# Alice.net
KiCad netlist of a schematic drawn in EAGLE
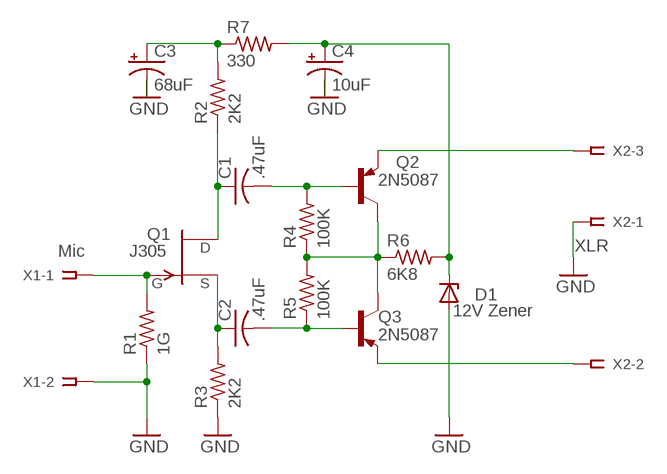
[diagram p0: schematic, sheet 1]

(export (version "E")
  (design (tool "Eeschema 10.0.6"))
  (components
    (comp (ref "C1")
      (value ".47uF")
      (footprint "eagle-import:C075-052X106")
      (libsource (lib "eagle-import") (part "C-US075-052X106"))
    )
    (comp (ref "C2")
      (value ".47uF")
      (footprint "eagle-import:C075-052X106")
      (libsource (lib "eagle-import") (part "C-US075-052X106"))
    )
    (comp (ref "C3")
      (value "68uF")
      (footprint "eagle-import:E3,5-10")
      (libsource (lib "eagle-import") (part "CPOL-USE3.5-10"))
    )
    (comp (ref "C4")
      (value "10uF")
      (footprint "eagle-import:E1,8-4")
      (libsource (lib "eagle-import") (part "CPOL-USE1.8-4"))
    )
    (comp (ref "D1")
      (value "12V Zener")
      (footprint "eagle-import:DO35Z10")
      (libsource (lib "eagle-import") (part "ZENER-DIODEDO35Z10"))
    )
    (comp (ref "Q1")
      (value "J305")
      (footprint "eagle-import:TO-92")
      (libsource (lib "eagle-import") (part "2N5950"))
    )
    (comp (ref "Q2")
      (value "2N5087")
      (footprint "eagle-import:TO92-EBC-OVAL")
      (libsource (lib "eagle-import") (part "2N2907"))
    )
    (comp (ref "Q3")
      (value "2N5087")
      (footprint "eagle-import:TO92-EBC-OVAL")
      (libsource (lib "eagle-import") (part "2N2907"))
    )
    (comp (ref "R1")
      (value "1G")
      (footprint "eagle-import:0204_7")
      (libsource (lib "eagle-import") (part "R-US_0204/7"))
    )
    (comp (ref "R2")
      (value "2K2")
      (footprint "eagle-import:0204_7")
      (libsource (lib "eagle-import") (part "R-US_0204/7"))
    )
    (comp (ref "R3")
      (value "2K2")
      (footprint "eagle-import:0204_7")
      (libsource (lib "eagle-import") (part "R-US_0204/7"))
    )
    (comp (ref "R4")
      (value "100K")
      (footprint "eagle-import:0204_7")
      (libsource (lib "eagle-import") (part "R-US_0204/7"))
    )
    (comp (ref "R5")
      (value "100K")
      (footprint "eagle-import:0204_7")
      (libsource (lib "eagle-import") (part "R-US_0204/7"))
    )
    (comp (ref "R6")
      (value "6K8")
      (footprint "eagle-import:0204_7")
      (libsource (lib "eagle-import") (part "R-US_0204/7"))
    )
    (comp (ref "R7")
      (value "330")
      (footprint "eagle-import:0204_7")
      (libsource (lib "eagle-import") (part "R-US_0204/7"))
    )
    (comp (ref "X1")
      (value "Mic")
      (footprint "eagle-import:SSW-101-02-S-D")
      (fields (field (name "MPN") "SSW-101-02-S-D"))
      (libsource (lib "eagle-import") (part "SSW-101-02-S-D"))
    )
    (comp (ref "X2")
      (value "XLR")
      (footprint "eagle-import:SSW-101-02-S-T")
      (fields (field (name "MPN") "SSW-101-02-S-T"))
      (libsource (lib "eagle-import") (part "SSW-101-02-S-T"))
    )
  )
  (nets
    (net (code "1") (name "GND") (class "Default")
      (node (ref "C3") (pin "-") (pinfunction "-_-") (pintype "passive"))
      (node (ref "C4") (pin "-") (pinfunction "-_-") (pintype "passive"))
      (node (ref "D1") (pin "A") (pinfunction "A_A") (pintype "passive"))
      (node (ref "R1") (pin "1") (pinfunction "1_1") (pintype "passive"))
      (node (ref "R3") (pin "1") (pinfunction "1_1") (pintype "passive"))
      (node (ref "X1") (pin "2") (pinfunction "1_2") (pintype "passive"))
      (node (ref "X2") (pin "1") (pinfunction "1_1") (pintype "passive"))
    )
    (net (code "2") (name "Net-(C1-Pad2)") (class "Default")
      (node (ref "C1") (pin "2") (pinfunction "2_2") (pintype "passive"))
      (node (ref "Q2") (pin "B") (pinfunction "B_B") (pintype "passive"))
      (node (ref "R4") (pin "2") (pinfunction "2_2") (pintype "passive"))
    )
    (net (code "3") (name "Net-(C2-Pad2)") (class "Default")
      (node (ref "C2") (pin "2") (pinfunction "2_2") (pintype "passive"))
      (node (ref "Q3") (pin "B") (pinfunction "B_B") (pintype "passive"))
      (node (ref "R5") (pin "1") (pinfunction "1_1") (pintype "passive"))
    )
    (net (code "4") (name "Net-(C3-Pad+)") (class "Default")
      (node (ref "C3") (pin "+") (pinfunction "+_+") (pintype "passive"))
      (node (ref "R2") (pin "2") (pinfunction "2_2") (pintype "passive"))
      (node (ref "R7") (pin "1") (pinfunction "1_1") (pintype "passive"))
    )
    (net (code "5") (name "Net-(C4-Pad+)") (class "Default")
      (node (ref "C4") (pin "+") (pinfunction "+_+") (pintype "passive"))
      (node (ref "D1") (pin "C") (pinfunction "C_C") (pintype "passive"))
      (node (ref "R6") (pin "2") (pinfunction "2_2") (pintype "passive"))
      (node (ref "R7") (pin "2") (pinfunction "2_2") (pintype "passive"))
    )
    (net (code "6") (name "Net-(Q1-D)") (class "Default")
      (node (ref "C1") (pin "1") (pinfunction "1_1") (pintype "passive"))
      (node (ref "Q1") (pin "3") (pinfunction "D_3") (pintype "passive"))
      (node (ref "R2") (pin "1") (pinfunction "1_1") (pintype "passive"))
    )
    (net (code "7") (name "Net-(Q1-G)") (class "Default")
      (node (ref "Q1") (pin "1") (pinfunction "G_1") (pintype "passive"))
      (node (ref "R1") (pin "2") (pinfunction "2_2") (pintype "passive"))
      (node (ref "X1") (pin "1") (pinfunction "1_1") (pintype "passive"))
    )
    (net (code "8") (name "Net-(Q1-S)") (class "Default")
      (node (ref "C2") (pin "1") (pinfunction "1_1") (pintype "passive"))
      (node (ref "Q1") (pin "2") (pinfunction "S_2") (pintype "passive"))
      (node (ref "R3") (pin "2") (pinfunction "2_2") (pintype "passive"))
    )
    (net (code "9") (name "Net-(Q2-PadC)") (class "Default")
      (node (ref "Q2") (pin "C") (pinfunction "C_C") (pintype "passive"))
      (node (ref "Q3") (pin "C") (pinfunction "C_C") (pintype "passive"))
      (node (ref "R4") (pin "1") (pinfunction "1_1") (pintype "passive"))
      (node (ref "R5") (pin "2") (pinfunction "2_2") (pintype "passive"))
      (node (ref "R6") (pin "1") (pinfunction "1_1") (pintype "passive"))
    )
    (net (code "10") (name "Net-(X2B-1)") (class "Default")
      (node (ref "Q3") (pin "E") (pinfunction "E_E") (pintype "passive"))
      (node (ref "X2") (pin "2") (pinfunction "1_2") (pintype "passive"))
    )
    (net (code "11") (name "Net-(X2C-1)") (class "Default")
      (node (ref "Q2") (pin "E") (pinfunction "E_E") (pintype "passive"))
      (node (ref "X2") (pin "3") (pinfunction "1_3") (pintype "passive"))
    )
  )
)
